# Audio_Actual.net
KiCad netlist of a schematic drawn in Altium Designer
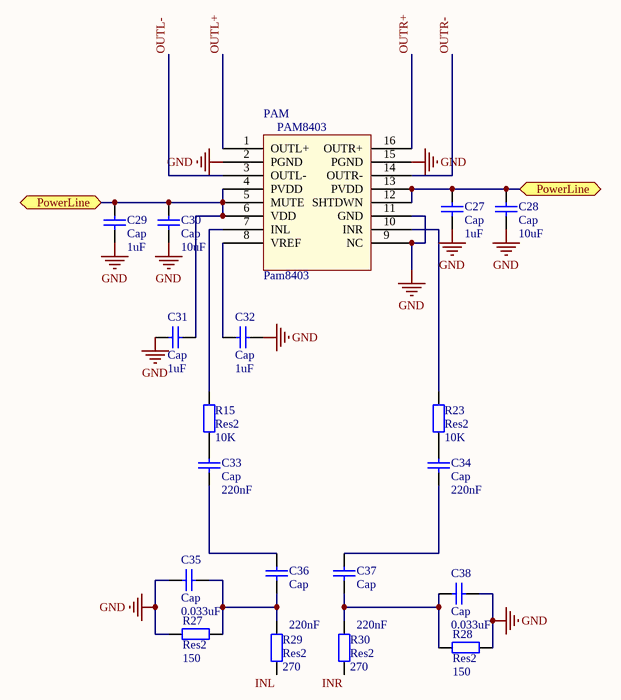
[diagram p0: Audio_Actual.SchDoc]

(export (version "E")
  (design (tool "Eeschema 10.0.6"))
  (components
    (comp (ref "C27")
      (value "Cap")
      (footprint "0805")
      (description "Capacitor")
      (fields (field (name "ALTIUM_VALUE") "1uF") (field (name "PUBLISHER") "Altium Limited"))
      (libsource (lib "Miscellaneous Devices") (part "Cap"))
    )
    (comp (ref "C28")
      (value "Cap")
      (footprint "0805")
      (description "Capacitor")
      (fields (field (name "ALTIUM_VALUE") "10uF") (field (name "PUBLISHER") "Altium Limited"))
      (libsource (lib "Miscellaneous Devices") (part "Cap"))
    )
    (comp (ref "C29")
      (value "Cap")
      (footprint "0805")
      (description "Capacitor")
      (fields (field (name "ALTIUM_VALUE") "1uF") (field (name "PUBLISHER") "Altium Limited"))
      (libsource (lib "Miscellaneous Devices") (part "Cap"))
    )
    (comp (ref "C30")
      (value "Cap")
      (footprint "0805")
      (description "Capacitor")
      (fields (field (name "ALTIUM_VALUE") "10uF") (field (name "PUBLISHER") "Altium Limited"))
      (libsource (lib "Miscellaneous Devices") (part "Cap"))
    )
    (comp (ref "C31")
      (value "Cap")
      (footprint "0805")
      (description "Capacitor")
      (fields (field (name "ALTIUM_VALUE") "1uF") (field (name "PUBLISHER") "Altium Limited"))
      (libsource (lib "Miscellaneous Devices") (part "Cap"))
    )
    (comp (ref "C32")
      (value "Cap")
      (footprint "0805")
      (description "Capacitor")
      (fields (field (name "ALTIUM_VALUE") "1uF") (field (name "PUBLISHER") "Altium Limited"))
      (libsource (lib "Miscellaneous Devices") (part "Cap"))
    )
    (comp (ref "C33")
      (value "Cap")
      (footprint "0805")
      (description "Capacitor")
      (fields (field (name "ALTIUM_VALUE") "220nF") (field (name "PUBLISHER") "Altium Limited"))
      (libsource (lib "Miscellaneous Devices") (part "Cap"))
    )
    (comp (ref "C34")
      (value "Cap")
      (footprint "0805")
      (description "Capacitor")
      (fields (field (name "ALTIUM_VALUE") "220nF") (field (name "PUBLISHER") "Altium Limited"))
      (libsource (lib "Miscellaneous Devices") (part "Cap"))
    )
    (comp (ref "C35")
      (value "Cap")
      (footprint "0805")
      (description "Capacitor")
      (fields (field (name "ALTIUM_VALUE") "0.033uF") (field (name "PUBLISHER") "Altium Limited"))
      (libsource (lib "Miscellaneous Devices") (part "Cap"))
    )
    (comp (ref "C36")
      (value "Cap")
      (footprint "RES-1206in")
      (description "Capacitor")
      (fields (field (name "ALTIUM_VALUE") "220nF") (field (name "PUBLISHER") "Altium Limited"))
      (libsource (lib "Miscellaneous Devices") (part "Cap"))
    )
    (comp (ref "C37")
      (value "Cap")
      (footprint "RES-1206in")
      (description "Capacitor")
      (fields (field (name "ALTIUM_VALUE") "220nF") (field (name "PUBLISHER") "Altium Limited"))
      (libsource (lib "Miscellaneous Devices") (part "Cap"))
    )
    (comp (ref "C38")
      (value "Cap")
      (footprint "0805")
      (description "Capacitor")
      (fields (field (name "ALTIUM_VALUE") "0.033uF") (field (name "PUBLISHER") "Altium Limited"))
      (libsource (lib "Miscellaneous Devices") (part "Cap"))
    )
    (comp (ref "PAM")
      (value "Pam8403")
      (footprint "pam8403 Sop16")
      (libsource (lib "Game Boy") (part "Pam8403"))
    )
    (comp (ref "R15")
      (value "Res2")
      (footprint "0805")
      (description "Resistor")
      (fields (field (name "ALTIUM_VALUE") "10K") (field (name "PUBLISHER") "Altium Limited"))
      (libsource (lib "") (part "Res2_1"))
    )
    (comp (ref "R23")
      (value "Res2")
      (footprint "0805")
      (description "Resistor")
      (fields (field (name "ALTIUM_VALUE") "10K") (field (name "PUBLISHER") "Altium Limited"))
      (libsource (lib "") (part "Res2_1"))
    )
    (comp (ref "R27")
      (value "Res2")
      (footprint "0805")
      (description "Resistor")
      (fields (field (name "ALTIUM_VALUE") "150") (field (name "PUBLISHER") "Altium Limited"))
      (libsource (lib "Miscellaneous Devices") (part "Res2"))
    )
    (comp (ref "R28")
      (value "Res2")
      (footprint "0805")
      (description "Resistor")
      (fields (field (name "ALTIUM_VALUE") "150") (field (name "PUBLISHER") "Altium Limited"))
      (libsource (lib "Miscellaneous Devices") (part "Res2"))
    )
    (comp (ref "R29")
      (value "Res2")
      (footprint "0805")
      (description "Resistor")
      (fields (field (name "ALTIUM_VALUE") "270") (field (name "PUBLISHER") "Altium Limited"))
      (libsource (lib "") (part "Res2_1"))
    )
    (comp (ref "R30")
      (value "Res2")
      (footprint "0805")
      (description "Resistor")
      (fields (field (name "ALTIUM_VALUE") "270") (field (name "PUBLISHER") "Altium Limited"))
      (libsource (lib "") (part "Res2_1"))
    )
  )
  (nets
    (net (code "1") (name "/INL") (class "Default")
      (node (ref "R29") (pin "1") (pinfunction "1_1") (pintype "passive"))
    )
    (net (code "2") (name "/INR") (class "Default")
      (node (ref "R30") (pin "1") (pinfunction "1_1") (pintype "passive"))
    )
    (net (code "3") (name "/OUTL+") (class "Default")
      (node (ref "PAM") (pin "1") (pinfunction "OUTL+_1") (pintype "passive"))
    )
    (net (code "4") (name "/OUTL-") (class "Default")
      (node (ref "PAM") (pin "3") (pinfunction "OUTL-_3") (pintype "passive"))
    )
    (net (code "5") (name "/OUTR+") (class "Default")
      (node (ref "PAM") (pin "16") (pinfunction "OUTR+_16") (pintype "passive"))
    )
    (net (code "6") (name "/OUTR-") (class "Default")
      (node (ref "PAM") (pin "14") (pinfunction "OUTR-_14") (pintype "passive"))
    )
    (net (code "7") (name "/PowerLine") (class "Default")
      (node (ref "C27") (pin "1") (pinfunction "1_1") (pintype "passive"))
      (node (ref "C28") (pin "2") (pinfunction "2_2") (pintype "passive"))
      (node (ref "C29") (pin "1") (pinfunction "1_1") (pintype "passive"))
      (node (ref "C30") (pin "2") (pinfunction "2_2") (pintype "passive"))
      (node (ref "C31") (pin "2") (pinfunction "2_2") (pintype "passive"))
      (node (ref "PAM") (pin "12") (pinfunction "SHTDWN_12") (pintype "passive"))
      (node (ref "PAM") (pin "13") (pinfunction "PVDD_13") (pintype "passive"))
      (node (ref "PAM") (pin "4") (pinfunction "PVDD_4") (pintype "passive"))
      (node (ref "PAM") (pin "5") (pinfunction "MUTE_5") (pintype "passive"))
      (node (ref "PAM") (pin "6") (pinfunction "VDD_6") (pintype "passive"))
    )
    (net (code "8") (name "GND") (class "Default")
      (node (ref "C27") (pin "2") (pinfunction "2_2") (pintype "passive"))
      (node (ref "C28") (pin "1") (pinfunction "1_1") (pintype "passive"))
      (node (ref "C29") (pin "2") (pinfunction "2_2") (pintype "passive"))
      (node (ref "C30") (pin "1") (pinfunction "1_1") (pintype "passive"))
      (node (ref "C31") (pin "1") (pinfunction "1_1") (pintype "passive"))
      (node (ref "C32") (pin "2") (pinfunction "2_2") (pintype "passive"))
      (node (ref "C35") (pin "2") (pinfunction "2_2") (pintype "passive"))
      (node (ref "C38") (pin "1") (pinfunction "1_1") (pintype "passive"))
      (node (ref "PAM") (pin "11") (pinfunction "GND_11") (pintype "passive"))
      (node (ref "PAM") (pin "15") (pinfunction "PGND_15") (pintype "passive"))
      (node (ref "PAM") (pin "2") (pinfunction "PGND_2") (pintype "passive"))
      (node (ref "PAM") (pin "9") (pinfunction "NC_9") (pintype "passive"))
      (node (ref "R27") (pin "2") (pinfunction "2_2") (pintype "passive"))
      (node (ref "R28") (pin "1") (pinfunction "1_1") (pintype "passive"))
    )
    (net (code "9") (name "Net-(C33-Pad1)") (class "Default")
      (node (ref "C33") (pin "1") (pinfunction "1_1") (pintype "passive"))
      (node (ref "C36") (pin "2") (pinfunction "2_2") (pintype "passive"))
    )
    (net (code "10") (name "Net-(C33-Pad2)") (class "Default")
      (node (ref "C33") (pin "2") (pinfunction "2_2") (pintype "passive"))
      (node (ref "R15") (pin "1") (pinfunction "1_1") (pintype "passive"))
    )
    (net (code "11") (name "Net-(C34-Pad1)") (class "Default")
      (node (ref "C34") (pin "1") (pinfunction "1_1") (pintype "passive"))
      (node (ref "C37") (pin "2") (pinfunction "2_2") (pintype "passive"))
    )
    (net (code "12") (name "Net-(C34-Pad2)") (class "Default")
      (node (ref "C34") (pin "2") (pinfunction "2_2") (pintype "passive"))
      (node (ref "R23") (pin "1") (pinfunction "1_1") (pintype "passive"))
    )
    (net (code "13") (name "Net-(C35-Pad1)") (class "Default")
      (node (ref "C35") (pin "1") (pinfunction "1_1") (pintype "passive"))
      (node (ref "C36") (pin "1") (pinfunction "1_1") (pintype "passive"))
      (node (ref "R27") (pin "1") (pinfunction "1_1") (pintype "passive"))
      (node (ref "R29") (pin "2") (pinfunction "2_2") (pintype "passive"))
    )
    (net (code "14") (name "Net-(C37-Pad1)") (class "Default")
      (node (ref "C37") (pin "1") (pinfunction "1_1") (pintype "passive"))
      (node (ref "C38") (pin "2") (pinfunction "2_2") (pintype "passive"))
      (node (ref "R28") (pin "2") (pinfunction "2_2") (pintype "passive"))
      (node (ref "R30") (pin "2") (pinfunction "2_2") (pintype "passive"))
    )
    (net (code "15") (name "Net-(PAM-INL)") (class "Default")
      (node (ref "PAM") (pin "7") (pinfunction "INL_7") (pintype "passive"))
      (node (ref "R15") (pin "2") (pinfunction "2_2") (pintype "passive"))
    )
    (net (code "16") (name "Net-(PAM-INR)") (class "Default")
      (node (ref "PAM") (pin "10") (pinfunction "INR_10") (pintype "passive"))
      (node (ref "R23") (pin "2") (pinfunction "2_2") (pintype "passive"))
    )
    (net (code "17") (name "Net-(PAM-VREF)") (class "Default")
      (node (ref "C32") (pin "1") (pinfunction "1_1") (pintype "passive"))
      (node (ref "PAM") (pin "8") (pinfunction "VREF_8") (pintype "passive"))
    )
  )
)
